# M_I_ext_sound.net
KiCad netlist of a schematic drawn in EAGLE
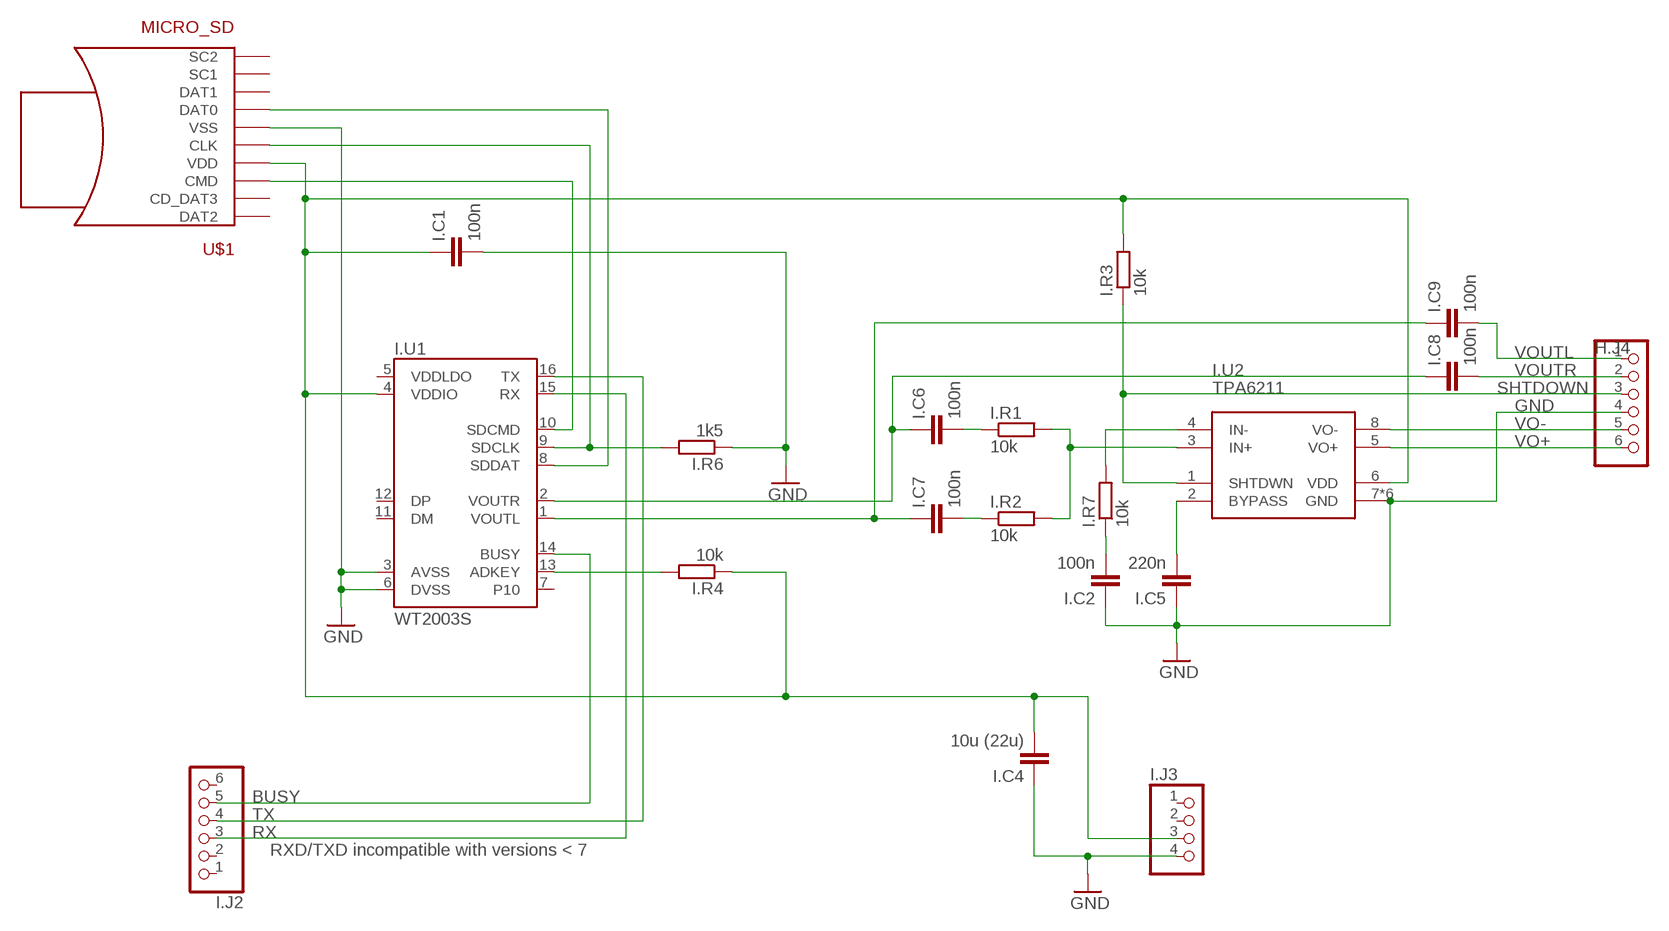
[diagram p0: schematic, sheet 1]

(export (version "E")
  (design (tool "Eeschema 10.0.6"))
  (components
    (comp (ref "H.J4")
      (value "PINHD-1X6")
      (footprint "eagle-import:1X06")
      (libsource (lib "eagle-import") (part "PINHD-1X6"))
    )
    (comp (ref "I.C1")
      (value "100n")
      (footprint "eagle-import:C0603")
      (libsource (lib "eagle-import") (part "C-EUC0603"))
    )
    (comp (ref "I.C2")
      (value "100n")
      (footprint "eagle-import:C0603")
      (libsource (lib "eagle-import") (part "C-EUC0603"))
    )
    (comp (ref "I.C4")
      (value "10u (22u)")
      (footprint "eagle-import:C0805")
      (libsource (lib "eagle-import") (part "C-EUC0805"))
    )
    (comp (ref "I.C5")
      (value "220n")
      (footprint "eagle-import:C0603")
      (libsource (lib "eagle-import") (part "C-EUC0603"))
    )
    (comp (ref "I.C6")
      (value "100n")
      (footprint "eagle-import:C0603")
      (libsource (lib "eagle-import") (part "C-EUC0603"))
    )
    (comp (ref "I.C7")
      (value "100n")
      (footprint "eagle-import:C0603")
      (libsource (lib "eagle-import") (part "C-EUC0603"))
    )
    (comp (ref "I.C8")
      (value "100n")
      (footprint "eagle-import:C0603")
      (libsource (lib "eagle-import") (part "C-EUC0603"))
    )
    (comp (ref "I.C9")
      (value "100n")
      (footprint "eagle-import:C0603")
      (libsource (lib "eagle-import") (part "C-EUC0603"))
    )
    (comp (ref "I.J2")
      (value "PINHD-1X6")
      (footprint "eagle-import:1X06")
      (libsource (lib "eagle-import") (part "PINHD-1X6"))
    )
    (comp (ref "I.J3")
      (value "PINHD-1X4")
      (footprint "eagle-import:1X04")
      (libsource (lib "eagle-import") (part "PINHD-1X4"))
    )
    (comp (ref "I.R1")
      (value "10k")
      (footprint "eagle-import:R0603")
      (libsource (lib "eagle-import") (part "R-EU_R0603"))
    )
    (comp (ref "I.R2")
      (value "10k")
      (footprint "eagle-import:R0603")
      (libsource (lib "eagle-import") (part "R-EU_R0603"))
    )
    (comp (ref "I.R3")
      (value "10k")
      (footprint "eagle-import:R0603")
      (libsource (lib "eagle-import") (part "R-EU_R0603"))
    )
    (comp (ref "I.R4")
      (value "10k")
      (footprint "eagle-import:R0603")
      (libsource (lib "eagle-import") (part "R-EU_R0603"))
    )
    (comp (ref "I.R6")
      (value "1k5")
      (footprint "eagle-import:R0603")
      (libsource (lib "eagle-import") (part "R-EU_R0603"))
    )
    (comp (ref "I.R7")
      (value "10k")
      (footprint "eagle-import:R0603")
      (libsource (lib "eagle-import") (part "R-EU_R0603"))
    )
    (comp (ref "I.U1")
      (value "WT2003S")
      (footprint "eagle-import:SO16")
      (libsource (lib "eagle-import") (part "WT2003S"))
    )
    (comp (ref "I.U2")
      (value "TPA6211")
      (footprint "eagle-import:MSOP-POWERPAD-8")
      (libsource (lib "eagle-import") (part "TPA6211"))
    )
    (comp (ref "U$1")
      (value "MICRO_SD")
      (footprint "eagle-import:MOCRO_SD")
      (libsource (lib "eagle-import") (part "MICRO_SD"))
    )
  )
  (nets
    (net (code "1") (name "/BUSY") (class "Default")
      (node (ref "I.J2") (pin "5") (pinfunction "5_5") (pintype "passive"))
      (node (ref "I.U1") (pin "14") (pinfunction "BUSY_14") (pintype "bidirectional"))
    )
    (net (code "2") (name "/RX") (class "Default")
      (node (ref "I.J2") (pin "3") (pinfunction "3_3") (pintype "passive"))
      (node (ref "I.U1") (pin "15") (pinfunction "RX_15") (pintype "bidirectional"))
    )
    (net (code "3") (name "/SHTDOWN") (class "Default")
      (node (ref "H.J4") (pin "3") (pinfunction "3_3") (pintype "passive"))
      (node (ref "I.R3") (pin "1") (pinfunction "1_1") (pintype "passive"))
      (node (ref "I.U2") (pin "1") (pinfunction "SHTDWN_1") (pintype "bidirectional"))
    )
    (net (code "4") (name "/TX") (class "Default")
      (node (ref "I.J2") (pin "4") (pinfunction "4_4") (pintype "passive"))
      (node (ref "I.U1") (pin "16") (pinfunction "TX_16") (pintype "bidirectional"))
    )
    (net (code "5") (name "/VO+") (class "Default")
      (node (ref "H.J4") (pin "6") (pinfunction "6_6") (pintype "passive"))
      (node (ref "I.U2") (pin "5") (pinfunction "VO+_5") (pintype "bidirectional"))
    )
    (net (code "6") (name "/VO-") (class "Default")
      (node (ref "H.J4") (pin "5") (pinfunction "5_5") (pintype "passive"))
      (node (ref "I.U2") (pin "8") (pinfunction "VO-_8") (pintype "bidirectional"))
    )
    (net (code "7") (name "/VOUTL") (class "Default")
      (node (ref "H.J4") (pin "1") (pinfunction "1_1") (pintype "passive"))
      (node (ref "I.C9") (pin "2") (pinfunction "2_2") (pintype "passive"))
    )
    (net (code "8") (name "/VOUTR") (class "Default")
      (node (ref "H.J4") (pin "2") (pinfunction "2_2") (pintype "passive"))
      (node (ref "I.C8") (pin "2") (pinfunction "2_2") (pintype "passive"))
    )
    (net (code "9") (name "GND") (class "Default")
      (node (ref "H.J4") (pin "4") (pinfunction "4_4") (pintype "passive"))
      (node (ref "I.C1") (pin "2") (pinfunction "2_2") (pintype "passive"))
      (node (ref "I.C2") (pin "1") (pinfunction "1_1") (pintype "passive"))
      (node (ref "I.C4") (pin "1") (pinfunction "1_1") (pintype "passive"))
      (node (ref "I.C5") (pin "1") (pinfunction "1_1") (pintype "passive"))
      (node (ref "I.J3") (pin "4") (pinfunction "4_4") (pintype "passive"))
      (node (ref "I.R6") (pin "1") (pinfunction "1_1") (pintype "passive"))
      (node (ref "I.U1") (pin "3") (pinfunction "AVSS_3") (pintype "bidirectional"))
      (node (ref "I.U1") (pin "6") (pinfunction "DVSS_6") (pintype "bidirectional"))
      (node (ref "I.U2") (pin "7") (pinfunction "GND_7") (pintype "bidirectional"))
      (node (ref "I.U2") (pin "9") (pinfunction "GND_9") (pintype "bidirectional"))
      (node (ref "I.U2") (pin "P$10") (pinfunction "GND_P$10") (pintype "bidirectional"))
      (node (ref "I.U2") (pin "P$11") (pinfunction "GND_P$11") (pintype "bidirectional"))
      (node (ref "I.U2") (pin "P$12") (pinfunction "GND_P$12") (pintype "bidirectional"))
      (node (ref "I.U2") (pin "P$13") (pinfunction "GND_P$13") (pintype "bidirectional"))
      (node (ref "U$1") (pin "6") (pinfunction "VSS_6") (pintype "bidirectional"))
      (node (ref "U$1") (pin "G1") (pinfunction "VSS_G1") (pintype "bidirectional"))
      (node (ref "U$1") (pin "G2") (pinfunction "VSS_G2") (pintype "bidirectional"))
      (node (ref "U$1") (pin "G3") (pinfunction "VSS_G3") (pintype "bidirectional"))
      (node (ref "U$1") (pin "G4") (pinfunction "VSS_G4") (pintype "bidirectional"))
    )
    (net (code "10") (name "Net-(I.C2-Pad2)") (class "Default")
      (node (ref "I.C2") (pin "2") (pinfunction "2_2") (pintype "passive"))
      (node (ref "I.R7") (pin "1") (pinfunction "1_1") (pintype "passive"))
    )
    (net (code "11") (name "Net-(I.C6-Pad2)") (class "Default")
      (node (ref "I.C6") (pin "2") (pinfunction "2_2") (pintype "passive"))
      (node (ref "I.R1") (pin "1") (pinfunction "1_1") (pintype "passive"))
    )
    (net (code "12") (name "Net-(I.C7-Pad2)") (class "Default")
      (node (ref "I.C7") (pin "2") (pinfunction "2_2") (pintype "passive"))
      (node (ref "I.R2") (pin "1") (pinfunction "1_1") (pintype "passive"))
    )
    (net (code "13") (name "Net-(I.U1-ADKEY)") (class "Default")
      (node (ref "I.R4") (pin "2") (pinfunction "2_2") (pintype "passive"))
      (node (ref "I.U1") (pin "13") (pinfunction "ADKEY_13") (pintype "bidirectional"))
    )
    (net (code "14") (name "Net-(I.U1-SDCLK)") (class "Default")
      (node (ref "I.R6") (pin "2") (pinfunction "2_2") (pintype "passive"))
      (node (ref "I.U1") (pin "9") (pinfunction "SDCLK_9") (pintype "bidirectional"))
      (node (ref "U$1") (pin "5") (pinfunction "CLK_5") (pintype "bidirectional"))
    )
    (net (code "15") (name "Net-(I.U1-SDCMD)") (class "Default")
      (node (ref "I.U1") (pin "10") (pinfunction "SDCMD_10") (pintype "bidirectional"))
      (node (ref "U$1") (pin "3") (pinfunction "CMD_3") (pintype "bidirectional"))
    )
    (net (code "16") (name "Net-(I.U1-SDDAT)") (class "Default")
      (node (ref "I.U1") (pin "8") (pinfunction "SDDAT_8") (pintype "bidirectional"))
      (node (ref "U$1") (pin "7") (pinfunction "DAT0_7") (pintype "bidirectional"))
    )
    (net (code "17") (name "Net-(I.U1-VDDIO)") (class "Default")
      (node (ref "I.C1") (pin "1") (pinfunction "1_1") (pintype "passive"))
      (node (ref "I.C4") (pin "2") (pinfunction "2_2") (pintype "passive"))
      (node (ref "I.J3") (pin "3") (pinfunction "3_3") (pintype "passive"))
      (node (ref "I.R3") (pin "2") (pinfunction "2_2") (pintype "passive"))
      (node (ref "I.R4") (pin "1") (pinfunction "1_1") (pintype "passive"))
      (node (ref "I.U1") (pin "4") (pinfunction "VDDIO_4") (pintype "bidirectional"))
      (node (ref "I.U2") (pin "6") (pinfunction "VDD_6") (pintype "bidirectional"))
      (node (ref "U$1") (pin "4") (pinfunction "VDD_4") (pintype "bidirectional"))
    )
    (net (code "18") (name "Net-(I.U1-VOUTL)") (class "Default")
      (node (ref "I.C7") (pin "1") (pinfunction "1_1") (pintype "passive"))
      (node (ref "I.C9") (pin "1") (pinfunction "1_1") (pintype "passive"))
      (node (ref "I.U1") (pin "1") (pinfunction "VOUTL_1") (pintype "bidirectional"))
    )
    (net (code "19") (name "Net-(I.U1-VOUTR)") (class "Default")
      (node (ref "I.C6") (pin "1") (pinfunction "1_1") (pintype "passive"))
      (node (ref "I.C8") (pin "1") (pinfunction "1_1") (pintype "passive"))
      (node (ref "I.U1") (pin "2") (pinfunction "VOUTR_2") (pintype "bidirectional"))
    )
    (net (code "20") (name "Net-(I.U2-BYPASS)") (class "Default")
      (node (ref "I.C5") (pin "2") (pinfunction "2_2") (pintype "passive"))
      (node (ref "I.U2") (pin "2") (pinfunction "BYPASS_2") (pintype "bidirectional"))
    )
    (net (code "21") (name "Net-(I.U2-IN+)") (class "Default")
      (node (ref "I.R1") (pin "2") (pinfunction "2_2") (pintype "passive"))
      (node (ref "I.R2") (pin "2") (pinfunction "2_2") (pintype "passive"))
      (node (ref "I.U2") (pin "3") (pinfunction "IN+_3") (pintype "bidirectional"))
    )
    (net (code "22") (name "Net-(I.U2-IN-)") (class "Default")
      (node (ref "I.R7") (pin "2") (pinfunction "2_2") (pintype "passive"))
      (node (ref "I.U2") (pin "4") (pinfunction "IN-_4") (pintype "bidirectional"))
    )
    (net (code "23") (name "unconnected-(I.J2-Pad1)") (class "Default")
      (node (ref "I.J2") (pin "1") (pinfunction "1_1") (pintype "passive"))
    )
    (net (code "24") (name "unconnected-(I.J2-Pad2)") (class "Default")
      (node (ref "I.J2") (pin "2") (pinfunction "2_2") (pintype "passive"))
    )
    (net (code "25") (name "unconnected-(I.J2-Pad6)") (class "Default")
      (node (ref "I.J2") (pin "6") (pinfunction "6_6") (pintype "passive"))
    )
    (net (code "26") (name "unconnected-(I.J3-Pad1)") (class "Default")
      (node (ref "I.J3") (pin "1") (pinfunction "1_1") (pintype "passive"))
    )
    (net (code "27") (name "unconnected-(I.J3-Pad2)") (class "Default")
      (node (ref "I.J3") (pin "2") (pinfunction "2_2") (pintype "passive"))
    )
    (net (code "28") (name "unconnected-(I.U1-DM-Pad11)") (class "Default")
      (node (ref "I.U1") (pin "11") (pinfunction "DM_11") (pintype "bidirectional"))
    )
    (net (code "29") (name "unconnected-(I.U1-DP-Pad12)") (class "Default")
      (node (ref "I.U1") (pin "12") (pinfunction "DP_12") (pintype "bidirectional"))
    )
    (net (code "30") (name "unconnected-(I.U1-P10-Pad7)") (class "Default")
      (node (ref "I.U1") (pin "7") (pinfunction "P10_7") (pintype "bidirectional"))
    )
    (net (code "31") (name "unconnected-(I.U1-VDDLDO-Pad5)") (class "Default")
      (node (ref "I.U1") (pin "5") (pinfunction "VDDLDO_5") (pintype "bidirectional"))
    )
    (net (code "32") (name "unconnected-(U$1-CD_DAT3-Pad2)") (class "Default")
      (node (ref "U$1") (pin "2") (pinfunction "CD_DAT3_2") (pintype "bidirectional"))
    )
    (net (code "33") (name "unconnected-(U$1-DAT1-Pad8)") (class "Default")
      (node (ref "U$1") (pin "8") (pinfunction "DAT1_8") (pintype "bidirectional"))
    )
    (net (code "34") (name "unconnected-(U$1-DAT2-Pad1)") (class "Default")
      (node (ref "U$1") (pin "1") (pinfunction "DAT2_1") (pintype "bidirectional"))
    )
    (net (code "35") (name "unconnected-(U$1-SC1-PadS1)") (class "Default")
      (node (ref "U$1") (pin "S1") (pinfunction "SC1_S1") (pintype "bidirectional"))
    )
    (net (code "36") (name "unconnected-(U$1-SC2-PadS2)") (class "Default")
      (node (ref "U$1") (pin "S2") (pinfunction "SC2_S2") (pintype "bidirectional"))
    )
  )
)
